# CH340G9T-R0.net
KiCad netlist of a schematic drawn in Altium Designer
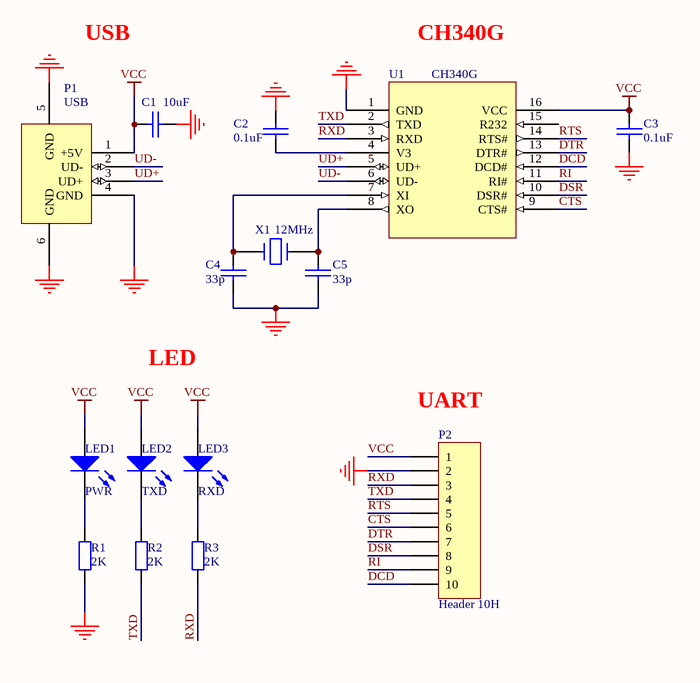
[diagram p0: CH340G9T-R0.SchDoc]

(export (version "E")
  (design (tool "Eeschema 10.0.6"))
  (components
    (comp (ref "C1")
      (value "10uF")
      (footprint "3216_C")
      (description "Capacitor")
      (libsource (lib "") (part "CAP_1"))
    )
    (comp (ref "C2")
      (value "0.1uF")
      (footprint "0603_C")
      (description "Capacitor")
      (libsource (lib "") (part "CAP_1"))
    )
    (comp (ref "C3")
      (value "0.1uF")
      (footprint "0603_C")
      (description "Capacitor")
      (libsource (lib "") (part "CAP_1"))
    )
    (comp (ref "C4")
      (value "33p")
      (footprint "0603_C")
      (description "Capacitor")
      (libsource (lib "*") (part "CAP"))
    )
    (comp (ref "C5")
      (value "33p")
      (footprint "0603_C")
      (description "Capacitor")
      (libsource (lib "*") (part "CAP"))
    )
    (comp (ref "LED1")
      (value "PWR")
      (footprint "0603+")
      (description "Typical RED, GREEN, YELLOW, AMBER GaAs LED")
      (libsource (lib "*") (part "LED2"))
    )
    (comp (ref "LED2")
      (value "TXD")
      (footprint "0603+")
      (description "Typical RED, GREEN, YELLOW, AMBER GaAs LED")
      (libsource (lib "*") (part "LED2"))
    )
    (comp (ref "LED3")
      (value "RXD")
      (footprint "0603+")
      (description "Typical RED, GREEN, YELLOW, AMBER GaAs LED")
      (libsource (lib "*") (part "LED2"))
    )
    (comp (ref "P1") (value "USB") (footprint "USBAM") (libsource (lib "*") (part "USB")))
    (comp (ref "P2")
      (value "Header 10H")
      (footprint "SIP10-2.54mm")
      (description "Header, 10-Pin, Right Angle")
      (fields (field (name "PUBLISHER") "Altium Limited"))
      (libsource (lib "Miscellaneous Connectors") (part "Header 10H"))
    )
    (comp (ref "R1")
      (value "2K")
      (footprint "0603")
      (description "Resistor")
      (libsource (lib "*") (part "Res2"))
    )
    (comp (ref "R2")
      (value "2K")
      (footprint "0603")
      (description "Resistor")
      (libsource (lib "*") (part "Res2"))
    )
    (comp (ref "R3")
      (value "2K")
      (footprint "0603")
      (description "Resistor")
      (libsource (lib "*") (part "Res2"))
    )
    (comp (ref "U1")
      (value "CH340G")
      (footprint "SOP16")
      (description "USB to TTL Serial / UART")
      (libsource (lib "*") (part "CH340G"))
    )
    (comp (ref "X1")
      (value "12MHz")
      (footprint "XT3225")
      (description "Crystal")
      (libsource (lib "*") (part "CRYSTAL"))
    )
  )
  (nets
    (net (code "1") (name "/CTS") (class "Default")
      (node (ref "P2") (pin "6") (pinfunction "6_6") (pintype "passive"))
      (node (ref "U1") (pin "9") (pinfunction "CTS#_9") (pintype "input"))
    )
    (net (code "2") (name "/DCD") (class "Default")
      (node (ref "P2") (pin "10") (pinfunction "10_10") (pintype "passive"))
      (node (ref "U1") (pin "12") (pinfunction "DCD#_12") (pintype "input"))
    )
    (net (code "3") (name "/DSR") (class "Default")
      (node (ref "P2") (pin "8") (pinfunction "8_8") (pintype "passive"))
      (node (ref "U1") (pin "10") (pinfunction "DSR#_10") (pintype "input"))
    )
    (net (code "4") (name "/DTR") (class "Default")
      (node (ref "P2") (pin "7") (pinfunction "7_7") (pintype "passive"))
      (node (ref "U1") (pin "13") (pinfunction "DTR#_13") (pintype "output"))
    )
    (net (code "5") (name "/RI") (class "Default")
      (node (ref "P2") (pin "9") (pinfunction "9_9") (pintype "passive"))
      (node (ref "U1") (pin "11") (pinfunction "RI#_11") (pintype "input"))
    )
    (net (code "6") (name "/RTS") (class "Default")
      (node (ref "P2") (pin "5") (pinfunction "5_5") (pintype "passive"))
      (node (ref "U1") (pin "14") (pinfunction "RTS#_14") (pintype "output"))
    )
    (net (code "7") (name "/RXD") (class "Default")
      (node (ref "P2") (pin "3") (pinfunction "3_3") (pintype "passive"))
      (node (ref "R3") (pin "2") (pinfunction "2_2") (pintype "passive"))
      (node (ref "U1") (pin "3") (pinfunction "RXD_3") (pintype "input"))
    )
    (net (code "8") (name "/TXD") (class "Default")
      (node (ref "P2") (pin "4") (pinfunction "4_4") (pintype "passive"))
      (node (ref "R2") (pin "2") (pinfunction "2_2") (pintype "passive"))
      (node (ref "U1") (pin "2") (pinfunction "TXD_2") (pintype "output"))
    )
    (net (code "9") (name "/UD+") (class "Default")
      (node (ref "P1") (pin "3") (pinfunction "UD+_3") (pintype "bidirectional"))
      (node (ref "U1") (pin "5") (pinfunction "UD+_5") (pintype "bidirectional"))
    )
    (net (code "10") (name "/UD-") (class "Default")
      (node (ref "P1") (pin "2") (pinfunction "UD-_2") (pintype "bidirectional"))
      (node (ref "U1") (pin "6") (pinfunction "UD-_6") (pintype "bidirectional"))
    )
    (net (code "11") (name "GND") (class "Default")
      (node (ref "C1") (pin "2") (pinfunction "2_2") (pintype "passive"))
      (node (ref "C2") (pin "2") (pinfunction "2_2") (pintype "passive"))
      (node (ref "C3") (pin "2") (pinfunction "2_2") (pintype "passive"))
      (node (ref "C4") (pin "2") (pinfunction "2_2") (pintype "passive"))
      (node (ref "C5") (pin "2") (pinfunction "2_2") (pintype "passive"))
      (node (ref "P1") (pin "4") (pinfunction "GND_4") (pintype "power_in"))
      (node (ref "P1") (pin "5") (pinfunction "GND_5") (pintype "power_in"))
      (node (ref "P1") (pin "6") (pinfunction "GND_6") (pintype "power_in"))
      (node (ref "P2") (pin "2") (pinfunction "2_2") (pintype "passive"))
      (node (ref "R1") (pin "2") (pinfunction "2_2") (pintype "passive"))
      (node (ref "U1") (pin "1") (pinfunction "GND_1") (pintype "power_in"))
    )
    (net (code "12") (name "Net-(LED1-K)") (class "Default")
      (node (ref "LED1") (pin "2") (pinfunction "K_2") (pintype "passive"))
      (node (ref "R1") (pin "1") (pinfunction "1_1") (pintype "passive"))
    )
    (net (code "13") (name "Net-(LED2-K)") (class "Default")
      (node (ref "LED2") (pin "2") (pinfunction "K_2") (pintype "passive"))
      (node (ref "R2") (pin "1") (pinfunction "1_1") (pintype "passive"))
    )
    (net (code "14") (name "Net-(LED3-K)") (class "Default")
      (node (ref "LED3") (pin "2") (pinfunction "K_2") (pintype "passive"))
      (node (ref "R3") (pin "1") (pinfunction "1_1") (pintype "passive"))
    )
    (net (code "15") (name "Net-(U1-V3)") (class "Default")
      (node (ref "C2") (pin "1") (pinfunction "1_1") (pintype "passive"))
      (node (ref "U1") (pin "4") (pinfunction "V3_4") (pintype "power_in"))
    )
    (net (code "16") (name "Net-(U1-XI)") (class "Default")
      (node (ref "C4") (pin "1") (pinfunction "1_1") (pintype "passive"))
      (node (ref "U1") (pin "7") (pinfunction "XI_7") (pintype "input"))
      (node (ref "X1") (pin "1") (pinfunction "1_1") (pintype "passive"))
    )
    (net (code "17") (name "Net-(U1-XO)") (class "Default")
      (node (ref "C5") (pin "1") (pinfunction "1_1") (pintype "passive"))
      (node (ref "U1") (pin "8") (pinfunction "XO_8") (pintype "output"))
      (node (ref "X1") (pin "3") (pinfunction "3_3") (pintype "passive"))
    )
    (net (code "18") (name "VCC") (class "Default")
      (node (ref "C1") (pin "1") (pinfunction "1_1") (pintype "passive"))
      (node (ref "C3") (pin "1") (pinfunction "1_1") (pintype "passive"))
      (node (ref "LED1") (pin "1") (pinfunction "A_1") (pintype "passive"))
      (node (ref "LED2") (pin "1") (pinfunction "A_1") (pintype "passive"))
      (node (ref "LED3") (pin "1") (pinfunction "A_1") (pintype "passive"))
      (node (ref "P1") (pin "1") (pinfunction "+5V_1") (pintype "power_in"))
      (node (ref "P2") (pin "1") (pinfunction "1_1") (pintype "passive"))
      (node (ref "U1") (pin "16") (pinfunction "VCC_16") (pintype "power_in"))
    )
    (net (code "19") (name "unconnected-(U1-R232-Pad15)") (class "Default")
      (node (ref "U1") (pin "15") (pinfunction "R232_15") (pintype "input"))
    )
  )
)
